# Connectors.net
KiCad netlist of a schematic drawn in Altium Designer
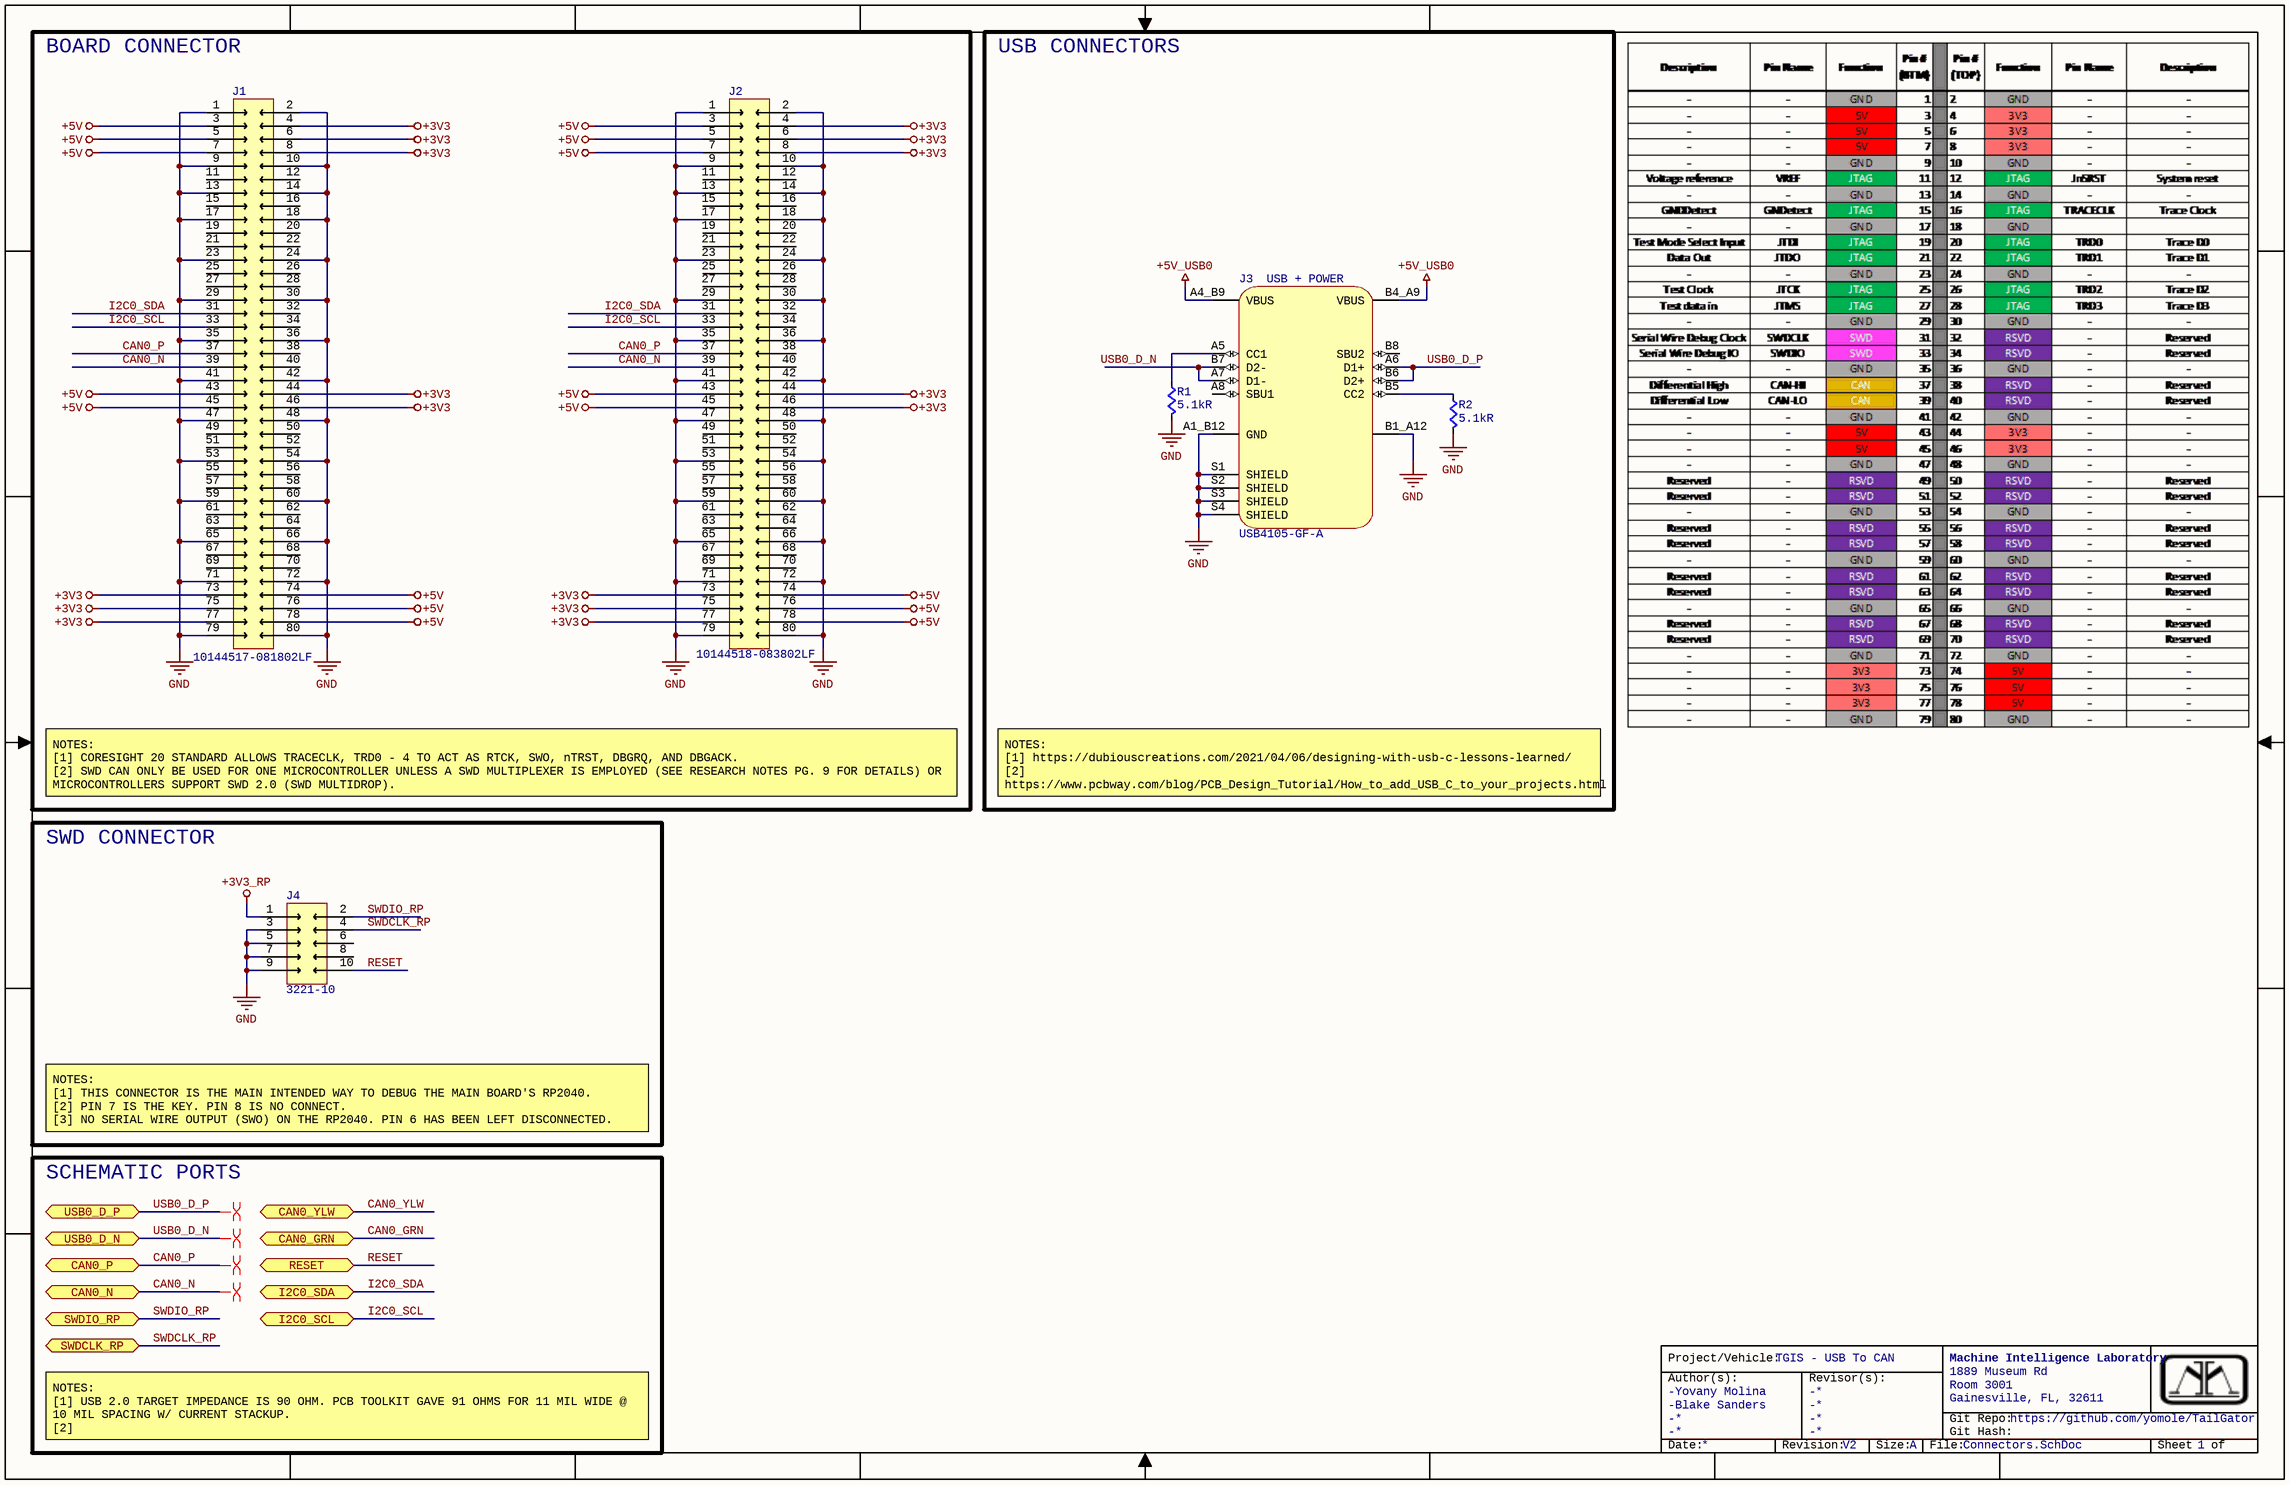
[diagram p0: Connectors.SchDoc]

(export (version "E")
  (design (tool "Eeschema 10.0.6"))
  (components
    (comp (ref "J1")
      (value "10144517-081802LF")
      (footprint "AMPHENOL_10144517-081802LF")
      (description "CONN RCPT 1 80POS SMD GOLD")
      (libsource (lib "TGIS") (part "10144517-081802LF"))
    )
    (comp (ref "J2")
      (value "10144518-083802LF")
      (footprint "AMPHENOL_10144518-083802LF")
      (description "CONN PLUG 3 80POS SMD GOLD")
      (libsource (lib "TGIS") (part "10144518-083802LF"))
    )
    (comp (ref "J3")
      (value "USB4105-GF-A")
      (footprint "GCT_USB4105-GF-A")
      (fields (field (name "MP") "USB4120-03-C_REVA"))
      (libsource (lib "TGIS") (part "USB4105-GF-A"))
    )
    (comp (ref "J4")
      (value "3221-10")
      (footprint "3220-10-0200-00")
      (description "Connector Header Surface Mount 10 position 0.050\" (1.27mm)")
      (libsource (lib "TGIS_Connectors") (part "3221-10-0300-00"))
    )
    (comp (ref "R1")
      (value "5.1kR")
      (footprint "RES0603")
      (description "Fixed Resistor, Metal Glaze/thick F")
      (fields (field (name "PART NUMBER") "RC0603FR-075K1L") (field (name "POWER") "100mW"))
      (libsource (lib "Parts") (part "Resistor"))
    )
    (comp (ref "R2")
      (value "5.1kR")
      (footprint "RES0603")
      (description "Fixed Resistor, Metal Glaze/thick F")
      (fields (field (name "PART NUMBER") "RC0603FR-075K1L") (field (name "POWER") "100mW"))
      (libsource (lib "Parts") (part "Resistor"))
    )
  )
  (nets
    (net (code "1") (name "+3V3") (class "Default")
      (node (ref "J1") (pin "4") (pinfunction "4_4") (pintype "passive"))
      (node (ref "J1") (pin "44") (pinfunction "44_44") (pintype "passive"))
      (node (ref "J1") (pin "46") (pinfunction "46_46") (pintype "passive"))
      (node (ref "J1") (pin "6") (pinfunction "6_6") (pintype "passive"))
      (node (ref "J1") (pin "73") (pinfunction "73_73") (pintype "passive"))
      (node (ref "J1") (pin "75") (pinfunction "75_75") (pintype "passive"))
      (node (ref "J1") (pin "77") (pinfunction "77_77") (pintype "passive"))
      (node (ref "J1") (pin "8") (pinfunction "8_8") (pintype "passive"))
      (node (ref "J2") (pin "4") (pinfunction "4_4") (pintype "passive"))
      (node (ref "J2") (pin "44") (pinfunction "44_44") (pintype "passive"))
      (node (ref "J2") (pin "46") (pinfunction "46_46") (pintype "passive"))
      (node (ref "J2") (pin "6") (pinfunction "6_6") (pintype "passive"))
      (node (ref "J2") (pin "73") (pinfunction "73_73") (pintype "passive"))
      (node (ref "J2") (pin "75") (pinfunction "75_75") (pintype "passive"))
      (node (ref "J2") (pin "77") (pinfunction "77_77") (pintype "passive"))
      (node (ref "J2") (pin "8") (pinfunction "8_8") (pintype "passive"))
    )
    (net (code "2") (name "+3V3_RP") (class "Default")
      (node (ref "J4") (pin "1") (pinfunction "1_1") (pintype "passive"))
    )
    (net (code "3") (name "+5V") (class "Default")
      (node (ref "J1") (pin "3") (pinfunction "3_3") (pintype "passive"))
      (node (ref "J1") (pin "43") (pinfunction "43_43") (pintype "passive"))
      (node (ref "J1") (pin "45") (pinfunction "45_45") (pintype "passive"))
      (node (ref "J1") (pin "5") (pinfunction "5_5") (pintype "passive"))
      (node (ref "J1") (pin "7") (pinfunction "7_7") (pintype "passive"))
      (node (ref "J1") (pin "74") (pinfunction "74_74") (pintype "passive"))
      (node (ref "J1") (pin "76") (pinfunction "76_76") (pintype "passive"))
      (node (ref "J1") (pin "78") (pinfunction "78_78") (pintype "passive"))
      (node (ref "J2") (pin "3") (pinfunction "3_3") (pintype "passive"))
      (node (ref "J2") (pin "43") (pinfunction "43_43") (pintype "passive"))
      (node (ref "J2") (pin "45") (pinfunction "45_45") (pintype "passive"))
      (node (ref "J2") (pin "5") (pinfunction "5_5") (pintype "passive"))
      (node (ref "J2") (pin "7") (pinfunction "7_7") (pintype "passive"))
      (node (ref "J2") (pin "74") (pinfunction "74_74") (pintype "passive"))
      (node (ref "J2") (pin "76") (pinfunction "76_76") (pintype "passive"))
      (node (ref "J2") (pin "78") (pinfunction "78_78") (pintype "passive"))
    )
    (net (code "4") (name "+5V_USB0") (class "Default")
      (node (ref "J3") (pin "A4_B9") (pinfunction "VBUS_A4_B9") (pintype "power_in"))
      (node (ref "J3") (pin "B4_A9") (pinfunction "VBUS_B4_A9") (pintype "power_in"))
    )
    (net (code "6") (name "/CAN0_N") (class "Default")
      (node (ref "J1") (pin "39") (pinfunction "39_39") (pintype "passive"))
      (node (ref "J2") (pin "39") (pinfunction "39_39") (pintype "passive"))
    )
    (net (code "7") (name "/CAN0_P") (class "Default")
      (node (ref "J1") (pin "37") (pinfunction "37_37") (pintype "passive"))
      (node (ref "J2") (pin "37") (pinfunction "37_37") (pintype "passive"))
    )
    (net (code "9") (name "/I2C0_SCL") (class "Default")
      (node (ref "J1") (pin "33") (pinfunction "33_33") (pintype "passive"))
      (node (ref "J2") (pin "33") (pinfunction "33_33") (pintype "passive"))
    )
    (net (code "10") (name "/I2C0_SDA") (class "Default")
      (node (ref "J1") (pin "31") (pinfunction "31_31") (pintype "passive"))
      (node (ref "J2") (pin "31") (pinfunction "31_31") (pintype "passive"))
    )
    (net (code "11") (name "/RESET") (class "Default")
      (node (ref "J4") (pin "10") (pinfunction "10_10") (pintype "passive"))
    )
    (net (code "12") (name "/SWDCLK_RP") (class "Default")
      (node (ref "J4") (pin "4") (pinfunction "4_4") (pintype "passive"))
    )
    (net (code "13") (name "/SWDIO_RP") (class "Default")
      (node (ref "J4") (pin "2") (pinfunction "2_2") (pintype "passive"))
    )
    (net (code "14") (name "/USB0_D_N") (class "Default")
      (node (ref "J3") (pin "A7") (pinfunction "D1-_A7") (pintype "bidirectional"))
      (node (ref "J3") (pin "B7") (pinfunction "D2-_B7") (pintype "bidirectional"))
    )
    (net (code "15") (name "/USB0_D_P") (class "Default")
      (node (ref "J3") (pin "A6") (pinfunction "D1+_A6") (pintype "bidirectional"))
      (node (ref "J3") (pin "B6") (pinfunction "D2+_B6") (pintype "bidirectional"))
    )
    (net (code "16") (name "GND") (class "Default")
      (node (ref "J1") (pin "1") (pinfunction "1_1") (pintype "passive"))
      (node (ref "J1") (pin "10") (pinfunction "10_10") (pintype "passive"))
      (node (ref "J1") (pin "13") (pinfunction "13_13") (pintype "passive"))
      (node (ref "J1") (pin "14") (pinfunction "14_14") (pintype "passive"))
      (node (ref "J1") (pin "17") (pinfunction "17_17") (pintype "passive"))
      (node (ref "J1") (pin "18") (pinfunction "18_18") (pintype "passive"))
      (node (ref "J1") (pin "2") (pinfunction "2_2") (pintype "passive"))
      (node (ref "J1") (pin "23") (pinfunction "23_23") (pintype "passive"))
      (node (ref "J1") (pin "24") (pinfunction "24_24") (pintype "passive"))
      (node (ref "J1") (pin "29") (pinfunction "29_29") (pintype "passive"))
      (node (ref "J1") (pin "30") (pinfunction "30_30") (pintype "passive"))
      (node (ref "J1") (pin "35") (pinfunction "35_35") (pintype "passive"))
      (node (ref "J1") (pin "36") (pinfunction "36_36") (pintype "passive"))
      (node (ref "J1") (pin "41") (pinfunction "41_41") (pintype "passive"))
      (node (ref "J1") (pin "42") (pinfunction "42_42") (pintype "passive"))
      (node (ref "J1") (pin "47") (pinfunction "47_47") (pintype "passive"))
      (node (ref "J1") (pin "48") (pinfunction "48_48") (pintype "passive"))
      (node (ref "J1") (pin "53") (pinfunction "53_53") (pintype "passive"))
      (node (ref "J1") (pin "54") (pinfunction "54_54") (pintype "passive"))
      (node (ref "J1") (pin "59") (pinfunction "59_59") (pintype "passive"))
      (node (ref "J1") (pin "60") (pinfunction "60_60") (pintype "passive"))
      (node (ref "J1") (pin "65") (pinfunction "65_65") (pintype "passive"))
      (node (ref "J1") (pin "66") (pinfunction "66_66") (pintype "passive"))
      (node (ref "J1") (pin "71") (pinfunction "71_71") (pintype "passive"))
      (node (ref "J1") (pin "72") (pinfunction "72_72") (pintype "passive"))
      (node (ref "J1") (pin "79") (pinfunction "79_79") (pintype "passive"))
      (node (ref "J1") (pin "80") (pinfunction "80_80") (pintype "passive"))
      (node (ref "J1") (pin "9") (pinfunction "9_9") (pintype "passive"))
      (node (ref "J2") (pin "1") (pinfunction "1_1") (pintype "passive"))
      (node (ref "J2") (pin "10") (pinfunction "10_10") (pintype "passive"))
      (node (ref "J2") (pin "13") (pinfunction "13_13") (pintype "passive"))
      (node (ref "J2") (pin "14") (pinfunction "14_14") (pintype "passive"))
      (node (ref "J2") (pin "17") (pinfunction "17_17") (pintype "passive"))
      (node (ref "J2") (pin "18") (pinfunction "18_18") (pintype "passive"))
      (node (ref "J2") (pin "2") (pinfunction "2_2") (pintype "passive"))
      (node (ref "J2") (pin "23") (pinfunction "23_23") (pintype "passive"))
      (node (ref "J2") (pin "24") (pinfunction "24_24") (pintype "passive"))
      (node (ref "J2") (pin "29") (pinfunction "29_29") (pintype "passive"))
      (node (ref "J2") (pin "30") (pinfunction "30_30") (pintype "passive"))
      (node (ref "J2") (pin "35") (pinfunction "35_35") (pintype "passive"))
      (node (ref "J2") (pin "36") (pinfunction "36_36") (pintype "passive"))
      (node (ref "J2") (pin "41") (pinfunction "41_41") (pintype "passive"))
      (node (ref "J2") (pin "42") (pinfunction "42_42") (pintype "passive"))
      (node (ref "J2") (pin "47") (pinfunction "47_47") (pintype "passive"))
      (node (ref "J2") (pin "48") (pinfunction "48_48") (pintype "passive"))
      (node (ref "J2") (pin "53") (pinfunction "53_53") (pintype "passive"))
      (node (ref "J2") (pin "54") (pinfunction "54_54") (pintype "passive"))
      (node (ref "J2") (pin "59") (pinfunction "59_59") (pintype "passive"))
      (node (ref "J2") (pin "60") (pinfunction "60_60") (pintype "passive"))
      (node (ref "J2") (pin "65") (pinfunction "65_65") (pintype "passive"))
      (node (ref "J2") (pin "66") (pinfunction "66_66") (pintype "passive"))
      (node (ref "J2") (pin "71") (pinfunction "71_71") (pintype "passive"))
      (node (ref "J2") (pin "72") (pinfunction "72_72") (pintype "passive"))
      (node (ref "J2") (pin "79") (pinfunction "79_79") (pintype "passive"))
      (node (ref "J2") (pin "80") (pinfunction "80_80") (pintype "passive"))
      (node (ref "J2") (pin "9") (pinfunction "9_9") (pintype "passive"))
      (node (ref "J3") (pin "A1_B12") (pinfunction "GND_A1_B12") (pintype "power_in"))
      (node (ref "J3") (pin "B1_A12") (pintype "power_in"))
      (node (ref "J3") (pin "S1") (pinfunction "SHIELD_S1") (pintype "passive"))
      (node (ref "J3") (pin "S2") (pinfunction "SHIELD_S2") (pintype "passive"))
      (node (ref "J3") (pin "S3") (pinfunction "SHIELD_S3") (pintype "passive"))
      (node (ref "J3") (pin "S4") (pinfunction "SHIELD_S4") (pintype "passive"))
      (node (ref "J4") (pin "3") (pinfunction "3_3") (pintype "passive"))
      (node (ref "J4") (pin "5") (pinfunction "5_5") (pintype "passive"))
      (node (ref "J4") (pin "7") (pinfunction "7_7") (pintype "passive"))
      (node (ref "J4") (pin "9") (pinfunction "9_9") (pintype "passive"))
      (node (ref "R1") (pin "1") (pinfunction "A_1") (pintype "passive"))
      (node (ref "R2") (pin "1") (pinfunction "A_1") (pintype "passive"))
    )
    (net (code "17") (name "Net-(J3-CC1)") (class "Default")
      (node (ref "J3") (pin "A5") (pinfunction "CC1_A5") (pintype "bidirectional"))
      (node (ref "R1") (pin "2") (pinfunction "B_2") (pintype "passive"))
    )
    (net (code "18") (name "Net-(J3-CC2)") (class "Default")
      (node (ref "J3") (pin "B5") (pinfunction "CC2_B5") (pintype "bidirectional"))
      (node (ref "R2") (pin "2") (pinfunction "B_2") (pintype "passive"))
    )
    (net (code "19") (name "unconnected-(J1-Pad11)") (class "Default")
      (node (ref "J1") (pin "11") (pinfunction "11_11") (pintype "passive"))
    )
    (net (code "20") (name "unconnected-(J1-Pad12)") (class "Default")
      (node (ref "J1") (pin "12") (pinfunction "12_12") (pintype "passive"))
    )
    (net (code "21") (name "unconnected-(J1-Pad15)") (class "Default")
      (node (ref "J1") (pin "15") (pinfunction "15_15") (pintype "passive"))
    )
    (net (code "22") (name "unconnected-(J1-Pad16)") (class "Default")
      (node (ref "J1") (pin "16") (pinfunction "16_16") (pintype "passive"))
    )
    (net (code "23") (name "unconnected-(J1-Pad19)") (class "Default")
      (node (ref "J1") (pin "19") (pinfunction "19_19") (pintype "passive"))
    )
    (net (code "24") (name "unconnected-(J1-Pad20)") (class "Default")
      (node (ref "J1") (pin "20") (pinfunction "20_20") (pintype "passive"))
    )
    (net (code "25") (name "unconnected-(J1-Pad21)") (class "Default")
      (node (ref "J1") (pin "21") (pinfunction "21_21") (pintype "passive"))
    )
    (net (code "26") (name "unconnected-(J1-Pad22)") (class "Default")
      (node (ref "J1") (pin "22") (pinfunction "22_22") (pintype "passive"))
    )
    (net (code "27") (name "unconnected-(J1-Pad25)") (class "Default")
      (node (ref "J1") (pin "25") (pinfunction "25_25") (pintype "passive"))
    )
    (net (code "28") (name "unconnected-(J1-Pad26)") (class "Default")
      (node (ref "J1") (pin "26") (pinfunction "26_26") (pintype "passive"))
    )
    (net (code "29") (name "unconnected-(J1-Pad27)") (class "Default")
      (node (ref "J1") (pin "27") (pinfunction "27_27") (pintype "passive"))
    )
    (net (code "30") (name "unconnected-(J1-Pad28)") (class "Default")
      (node (ref "J1") (pin "28") (pinfunction "28_28") (pintype "passive"))
    )
    (net (code "31") (name "unconnected-(J1-Pad32)") (class "Default")
      (node (ref "J1") (pin "32") (pinfunction "32_32") (pintype "passive"))
    )
    (net (code "32") (name "unconnected-(J1-Pad34)") (class "Default")
      (node (ref "J1") (pin "34") (pinfunction "34_34") (pintype "passive"))
    )
    (net (code "33") (name "unconnected-(J1-Pad38)") (class "Default")
      (node (ref "J1") (pin "38") (pinfunction "38_38") (pintype "passive"))
    )
    (net (code "34") (name "unconnected-(J1-Pad40)") (class "Default")
      (node (ref "J1") (pin "40") (pinfunction "40_40") (pintype "passive"))
    )
    (net (code "35") (name "unconnected-(J1-Pad49)") (class "Default")
      (node (ref "J1") (pin "49") (pinfunction "49_49") (pintype "passive"))
    )
    (net (code "36") (name "unconnected-(J1-Pad50)") (class "Default")
      (node (ref "J1") (pin "50") (pinfunction "50_50") (pintype "passive"))
    )
    (net (code "37") (name "unconnected-(J1-Pad51)") (class "Default")
      (node (ref "J1") (pin "51") (pinfunction "51_51") (pintype "passive"))
    )
    (net (code "38") (name "unconnected-(J1-Pad52)") (class "Default")
      (node (ref "J1") (pin "52") (pinfunction "52_52") (pintype "passive"))
    )
    (net (code "39") (name "unconnected-(J1-Pad55)") (class "Default")
      (node (ref "J1") (pin "55") (pinfunction "55_55") (pintype "passive"))
    )
    (net (code "40") (name "unconnected-(J1-Pad56)") (class "Default")
      (node (ref "J1") (pin "56") (pinfunction "56_56") (pintype "passive"))
    )
    (net (code "41") (name "unconnected-(J1-Pad57)") (class "Default")
      (node (ref "J1") (pin "57") (pinfunction "57_57") (pintype "passive"))
    )
    (net (code "42") (name "unconnected-(J1-Pad58)") (class "Default")
      (node (ref "J1") (pin "58") (pinfunction "58_58") (pintype "passive"))
    )
    (net (code "43") (name "unconnected-(J1-Pad61)") (class "Default")
      (node (ref "J1") (pin "61") (pinfunction "61_61") (pintype "passive"))
    )
    (net (code "44") (name "unconnected-(J1-Pad62)") (class "Default")
      (node (ref "J1") (pin "62") (pinfunction "62_62") (pintype "passive"))
    )
    (net (code "45") (name "unconnected-(J1-Pad63)") (class "Default")
      (node (ref "J1") (pin "63") (pinfunction "63_63") (pintype "passive"))
    )
    (net (code "46") (name "unconnected-(J1-Pad64)") (class "Default")
      (node (ref "J1") (pin "64") (pinfunction "64_64") (pintype "passive"))
    )
    (net (code "47") (name "unconnected-(J1-Pad67)") (class "Default")
      (node (ref "J1") (pin "67") (pinfunction "67_67") (pintype "passive"))
    )
    (net (code "48") (name "unconnected-(J1-Pad68)") (class "Default")
      (node (ref "J1") (pin "68") (pinfunction "68_68") (pintype "passive"))
    )
    (net (code "49") (name "unconnected-(J1-Pad69)") (class "Default")
      (node (ref "J1") (pin "69") (pinfunction "69_69") (pintype "passive"))
    )
    (net (code "50") (name "unconnected-(J1-Pad70)") (class "Default")
      (node (ref "J1") (pin "70") (pinfunction "70_70") (pintype "passive"))
    )
    (net (code "51") (name "unconnected-(J2-Pad11)") (class "Default")
      (node (ref "J2") (pin "11") (pinfunction "11_11") (pintype "passive"))
    )
    (net (code "52") (name "unconnected-(J2-Pad12)") (class "Default")
      (node (ref "J2") (pin "12") (pinfunction "12_12") (pintype "passive"))
    )
    (net (code "53") (name "unconnected-(J2-Pad15)") (class "Default")
      (node (ref "J2") (pin "15") (pinfunction "15_15") (pintype "passive"))
    )
    (net (code "54") (name "unconnected-(J2-Pad16)") (class "Default")
      (node (ref "J2") (pin "16") (pinfunction "16_16") (pintype "passive"))
    )
    (net (code "55") (name "unconnected-(J2-Pad19)") (class "Default")
      (node (ref "J2") (pin "19") (pinfunction "19_19") (pintype "passive"))
    )
    (net (code "56") (name "unconnected-(J2-Pad20)") (class "Default")
      (node (ref "J2") (pin "20") (pinfunction "20_20") (pintype "passive"))
    )
    (net (code "57") (name "unconnected-(J2-Pad21)") (class "Default")
      (node (ref "J2") (pin "21") (pinfunction "21_21") (pintype "passive"))
    )
    (net (code "58") (name "unconnected-(J2-Pad22)") (class "Default")
      (node (ref "J2") (pin "22") (pinfunction "22_22") (pintype "passive"))
    )
    (net (code "59") (name "unconnected-(J2-Pad25)") (class "Default")
      (node (ref "J2") (pin "25") (pinfunction "25_25") (pintype "passive"))
    )
    (net (code "60") (name "unconnected-(J2-Pad26)") (class "Default")
      (node (ref "J2") (pin "26") (pinfunction "26_26") (pintype "passive"))
    )
    (net (code "61") (name "unconnected-(J2-Pad27)") (class "Default")
      (node (ref "J2") (pin "27") (pinfunction "27_27") (pintype "passive"))
    )
    (net (code "62") (name "unconnected-(J2-Pad28)") (class "Default")
      (node (ref "J2") (pin "28") (pinfunction "28_28") (pintype "passive"))
    )
    (net (code "63") (name "unconnected-(J2-Pad32)") (class "Default")
      (node (ref "J2") (pin "32") (pinfunction "32_32") (pintype "passive"))
    )
    (net (code "64") (name "unconnected-(J2-Pad34)") (class "Default")
      (node (ref "J2") (pin "34") (pinfunction "34_34") (pintype "passive"))
    )
    (net (code "65") (name "unconnected-(J2-Pad38)") (class "Default")
      (node (ref "J2") (pin "38") (pinfunction "38_38") (pintype "passive"))
    )
    (net (code "66") (name "unconnected-(J2-Pad40)") (class "Default")
      (node (ref "J2") (pin "40") (pinfunction "40_40") (pintype "passive"))
    )
    (net (code "67") (name "unconnected-(J2-Pad49)") (class "Default")
      (node (ref "J2") (pin "49") (pinfunction "49_49") (pintype "passive"))
    )
    (net (code "68") (name "unconnected-(J2-Pad50)") (class "Default")
      (node (ref "J2") (pin "50") (pinfunction "50_50") (pintype "passive"))
    )
    (net (code "69") (name "unconnected-(J2-Pad51)") (class "Default")
      (node (ref "J2") (pin "51") (pinfunction "51_51") (pintype "passive"))
    )
    (net (code "70") (name "unconnected-(J2-Pad52)") (class "Default")
      (node (ref "J2") (pin "52") (pinfunction "52_52") (pintype "passive"))
    )
    (net (code "71") (name "unconnected-(J2-Pad55)") (class "Default")
      (node (ref "J2") (pin "55") (pinfunction "55_55") (pintype "passive"))
    )
    (net (code "72") (name "unconnected-(J2-Pad56)") (class "Default")
      (node (ref "J2") (pin "56") (pinfunction "56_56") (pintype "passive"))
    )
    (net (code "73") (name "unconnected-(J2-Pad57)") (class "Default")
      (node (ref "J2") (pin "57") (pinfunction "57_57") (pintype "passive"))
    )
    (net (code "74") (name "unconnected-(J2-Pad58)") (class "Default")
      (node (ref "J2") (pin "58") (pinfunction "58_58") (pintype "passive"))
    )
    (net (code "75") (name "unconnected-(J2-Pad61)") (class "Default")
      (node (ref "J2") (pin "61") (pinfunction "61_61") (pintype "passive"))
    )
    (net (code "76") (name "unconnected-(J2-Pad62)") (class "Default")
      (node (ref "J2") (pin "62") (pinfunction "62_62") (pintype "passive"))
    )
    (net (code "77") (name "unconnected-(J2-Pad63)") (class "Default")
      (node (ref "J2") (pin "63") (pinfunction "63_63") (pintype "passive"))
    )
    (net (code "78") (name "unconnected-(J2-Pad64)") (class "Default")
      (node (ref "J2") (pin "64") (pinfunction "64_64") (pintype "passive"))
    )
    (net (code "79") (name "unconnected-(J2-Pad67)") (class "Default")
      (node (ref "J2") (pin "67") (pinfunction "67_67") (pintype "passive"))
    )
    (net (code "80") (name "unconnected-(J2-Pad68)") (class "Default")
      (node (ref "J2") (pin "68") (pinfunction "68_68") (pintype "passive"))
    )
    (net (code "81") (name "unconnected-(J2-Pad69)") (class "Default")
      (node (ref "J2") (pin "69") (pinfunction "69_69") (pintype "passive"))
    )
    (net (code "82") (name "unconnected-(J2-Pad70)") (class "Default")
      (node (ref "J2") (pin "70") (pinfunction "70_70") (pintype "passive"))
    )
    (net (code "83") (name "unconnected-(J3-SBU1-PadA8)") (class "Default")
      (node (ref "J3") (pin "A8") (pinfunction "SBU1_A8") (pintype "bidirectional"))
    )
    (net (code "84") (name "unconnected-(J3-SBU2-PadB8)") (class "Default")
      (node (ref "J3") (pin "B8") (pinfunction "SBU2_B8") (pintype "bidirectional"))
    )
    (net (code "85") (name "unconnected-(J4-Pad6)") (class "Default")
      (node (ref "J4") (pin "6") (pinfunction "6_6") (pintype "passive"))
    )
    (net (code "86") (name "unconnected-(J4-Pad8)") (class "Default")
      (node (ref "J4") (pin "8") (pinfunction "8_8") (pintype "passive"))
    )
  )
)
